# DM3370_OV9782_1-2.net
KiCad netlist of a schematic drawn in Altium Designer
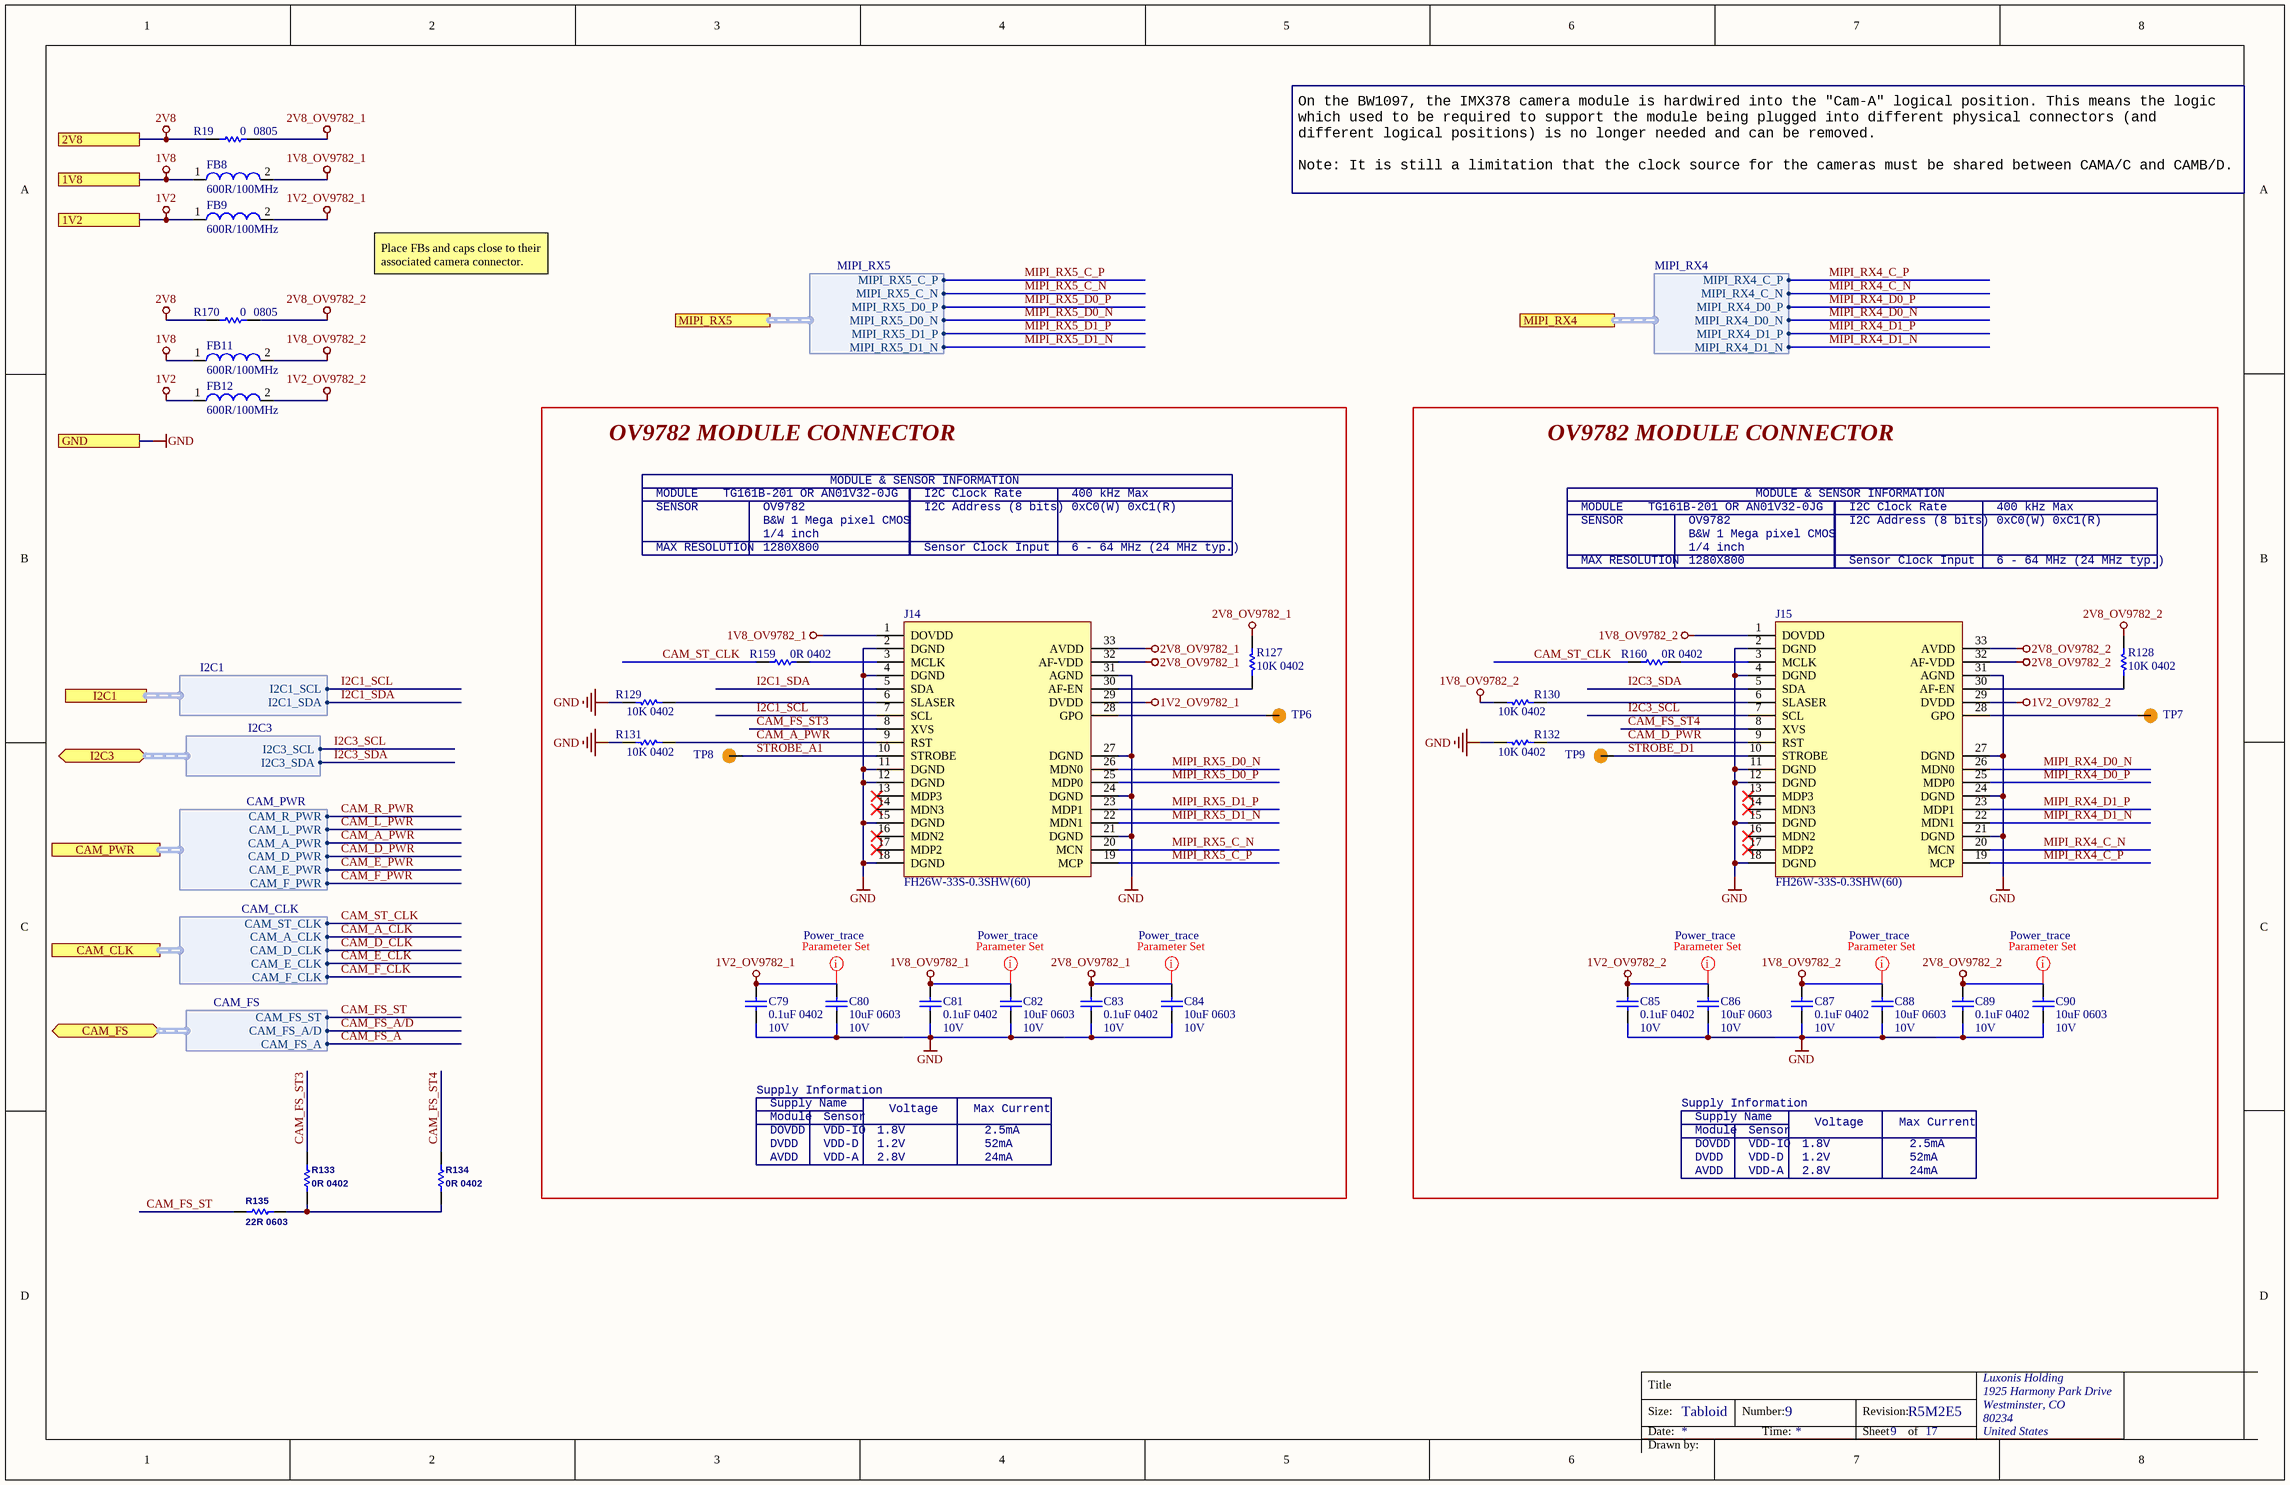
[diagram p0: DM3370_OV9782_1-2.SchDoc]

(export (version "E")
  (design (tool "Eeschema 10.0.6"))
  (components
    (comp (ref "C79")
      (value "0.1uF 0402")
      (footprint "CAP_Altium_Vault_Generic:CAPC0402(1005)70_L")
      (description "CAP CER 0.1UF 10V X7R 0402 5%")
      (fields (field (name "TOLERANCE") "5%") (field (name "VOLTAGE RATING") "10V"))
      (libsource (lib "LuxonisMaster") (part "GRM155R71A104JA01D"))
    )
    (comp (ref "C80")
      (value "10uF 0603")
      (footprint "CAP_Altium_Vault_Generic:CAPC0603(1608)100_L")
      (description "CAP CER 10UF 10V X5R 0603 20%")
      (fields (field (name "TOLERANCE") "20%") (field (name "VOLTAGE RATING") "10V"))
      (libsource (lib "LuxonisMaster") (part "GRM188R61A106ME69D"))
    )
    (comp (ref "C81")
      (value "0.1uF 0402")
      (footprint "CAP_Altium_Vault_Generic:CAPC0402(1005)70_L")
      (description "CAP CER 0.1UF 10V X7R 0402 5%")
      (fields (field (name "TOLERANCE") "5%") (field (name "VOLTAGE RATING") "10V"))
      (libsource (lib "LuxonisMaster") (part "GRM155R71A104JA01D"))
    )
    (comp (ref "C82")
      (value "10uF 0603")
      (footprint "CAP_Altium_Vault_Generic:CAPC0603(1608)100_L")
      (description "CAP CER 10UF 10V X5R 0603 20%")
      (fields (field (name "TOLERANCE") "20%") (field (name "VOLTAGE RATING") "10V"))
      (libsource (lib "LuxonisMaster") (part "GRM188R61A106ME69D"))
    )
    (comp (ref "C83")
      (value "0.1uF 0402")
      (footprint "CAP_Altium_Vault_Generic:CAPC0402(1005)70_L")
      (description "CAP CER 0.1UF 10V X7R 0402 5%")
      (fields (field (name "TOLERANCE") "5%") (field (name "VOLTAGE RATING") "10V"))
      (libsource (lib "LuxonisMaster") (part "GRM155R71A104JA01D"))
    )
    (comp (ref "C84")
      (value "10uF 0603")
      (footprint "CAP_Altium_Vault_Generic:CAPC0603(1608)100_L")
      (description "CAP CER 10UF 10V X5R 0603 20%")
      (fields (field (name "TOLERANCE") "20%") (field (name "VOLTAGE RATING") "10V"))
      (libsource (lib "LuxonisMaster") (part "GRM188R61A106ME69D"))
    )
    (comp (ref "C85")
      (value "0.1uF 0402")
      (footprint "CAP_Altium_Vault_Generic:CAPC0402(1005)70_L")
      (description "CAP CER 0.1UF 10V X7R 0402 5%")
      (fields (field (name "TOLERANCE") "5%") (field (name "VOLTAGE RATING") "10V"))
      (libsource (lib "LuxonisMaster") (part "GRM155R71A104JA01D"))
    )
    (comp (ref "C86")
      (value "10uF 0603")
      (footprint "CAP_Altium_Vault_Generic:CAPC0603(1608)100_L")
      (description "CAP CER 10UF 10V X5R 0603 20%")
      (fields (field (name "TOLERANCE") "20%") (field (name "VOLTAGE RATING") "10V"))
      (libsource (lib "LuxonisMaster") (part "GRM188R61A106ME69D"))
    )
    (comp (ref "C87")
      (value "0.1uF 0402")
      (footprint "CAP_Altium_Vault_Generic:CAPC0402(1005)70_L")
      (description "CAP CER 0.1UF 10V X7R 0402 5%")
      (fields (field (name "TOLERANCE") "5%") (field (name "VOLTAGE RATING") "10V"))
      (libsource (lib "LuxonisMaster") (part "GRM155R71A104JA01D"))
    )
    (comp (ref "C88")
      (value "10uF 0603")
      (footprint "CAP_Altium_Vault_Generic:CAPC0603(1608)100_L")
      (description "CAP CER 10UF 10V X5R 0603 20%")
      (fields (field (name "TOLERANCE") "20%") (field (name "VOLTAGE RATING") "10V"))
      (libsource (lib "LuxonisMaster") (part "GRM188R61A106ME69D"))
    )
    (comp (ref "C89")
      (value "0.1uF 0402")
      (footprint "CAP_Altium_Vault_Generic:CAPC0402(1005)70_L")
      (description "CAP CER 0.1UF 10V X7R 0402 5%")
      (fields (field (name "TOLERANCE") "5%") (field (name "VOLTAGE RATING") "10V"))
      (libsource (lib "LuxonisMaster") (part "GRM155R71A104JA01D"))
    )
    (comp (ref "C90")
      (value "10uF 0603")
      (footprint "CAP_Altium_Vault_Generic:CAPC0603(1608)100_L")
      (description "CAP CER 10UF 10V X5R 0603 20%")
      (fields (field (name "TOLERANCE") "20%") (field (name "VOLTAGE RATING") "10V"))
      (libsource (lib "LuxonisMaster") (part "GRM188R61A106ME69D"))
    )
    (comp (ref "FB8")
      (value "600R/100MHz")
      (footprint "LuxonisMaster:2508056017Y2")
      (description "FERRITE BEAD, 0.1OHM, 2A, 0805, 600R/100MHz")
      (fields (field (name "TOLERANCE") "25%"))
      (libsource (lib "LuxonisMaster") (part "2508056017Y2"))
    )
    (comp (ref "FB9")
      (value "600R/100MHz")
      (footprint "LuxonisMaster:2508056017Y2")
      (description "FERRITE BEAD, 0.1OHM, 2A, 0805, 600R/100MHz")
      (fields (field (name "TOLERANCE") "25%"))
      (libsource (lib "LuxonisMaster") (part "2508056017Y2"))
    )
    (comp (ref "FB11")
      (value "600R/100MHz")
      (footprint "LuxonisMaster:2508056017Y2")
      (description "FERRITE BEAD, 0.1OHM, 2A, 0805, 600R/100MHz")
      (fields (field (name "TOLERANCE") "25%"))
      (libsource (lib "LuxonisMaster") (part "2508056017Y2"))
    )
    (comp (ref "FB12")
      (value "600R/100MHz")
      (footprint "LuxonisMaster:2508056017Y2")
      (description "FERRITE BEAD, 0.1OHM, 2A, 0805, 600R/100MHz")
      (fields (field (name "TOLERANCE") "25%"))
      (libsource (lib "LuxonisMaster") (part "2508056017Y2"))
    )
    (comp (ref "J14")
      (value "FH26W-33S-0.3SHW(60)")
      (footprint "FH26W-33S-0.3SHW(60)")
      (description "FFC/FPC Connector, 33 Contact(s), 1 Row(s), Female, Right Angle, Surface Mount Terminal")
      (libsource (lib "Luxonis LLC") (part "FH26W-33S-0.3SHW(60)"))
    )
    (comp (ref "J15")
      (value "FH26W-33S-0.3SHW(60)")
      (footprint "FH26W-33S-0.3SHW(60)")
      (description "FFC/FPC Connector, 33 Contact(s), 1 Row(s), Female, Right Angle, Surface Mount Terminal")
      (libsource (lib "Luxonis LLC") (part "FH26W-33S-0.3SHW(60)"))
    )
    (comp (ref "R19")
      (value "0")
      (footprint "RESC0805(2012)_L")
      (description "RES SMD 0 OHM 1% 1/8W 0805")
      (fields (field (name "CASE/PACKAGE") "0805") (field (name "Comment") "CRCW08050000Z0EA"))
      (libsource (lib "Luxonis LLC") (part "Default resistor symbol"))
    )
    (comp (ref "R127")
      (value "10K 0402")
      (footprint "RES_Altium_Vault_Generic:RESC0402(1005)_L")
      (fields (field (name "TOLERANCE") "1%"))
      (libsource (lib "LuxonisMaster") (part "RC0402FR-1310KL"))
    )
    (comp (ref "R128")
      (value "10K 0402")
      (footprint "RES_Altium_Vault_Generic:RESC0402(1005)_L")
      (fields (field (name "TOLERANCE") "1%"))
      (libsource (lib "LuxonisMaster") (part "RC0402FR-1310KL"))
    )
    (comp (ref "R129")
      (value "10K 0402")
      (footprint "RES_Altium_Vault_Generic:RESC0402(1005)_L")
      (fields (field (name "TOLERANCE") "1%"))
      (libsource (lib "LuxonisMaster") (part "RC0402FR-1310KL"))
    )
    (comp (ref "R130")
      (value "10K 0402")
      (footprint "RES_Altium_Vault_Generic:RESC0402(1005)_L")
      (fields (field (name "TOLERANCE") "1%"))
      (libsource (lib "LuxonisMaster") (part "RC0402FR-1310KL"))
    )
    (comp (ref "R131")
      (value "10K 0402")
      (footprint "RES_Altium_Vault_Generic:RESC0402(1005)_L")
      (fields (field (name "TOLERANCE") "1%"))
      (libsource (lib "LuxonisMaster") (part "RC0402FR-1310KL"))
    )
    (comp (ref "R132")
      (value "10K 0402")
      (footprint "RES_Altium_Vault_Generic:RESC0402(1005)_L")
      (fields (field (name "TOLERANCE") "1%"))
      (libsource (lib "LuxonisMaster") (part "RC0402FR-1310KL"))
    )
    (comp (ref "R133")
      (value "0R 0402")
      (footprint "RES_Altium_Vault_Generic:RESC0402(1005)_L")
      (description "RES SMD 0 OHM JUMPER 1/16W 0402")
      (fields (field (name "TOLERANCE") "5%"))
      (libsource (lib "LuxonisMaster") (part "CRCW04020000Z0ED"))
    )
    (comp (ref "R134")
      (value "0R 0402")
      (footprint "RES_Altium_Vault_Generic:RESC0402(1005)_L")
      (description "RES SMD 0 OHM JUMPER 1/16W 0402")
      (fields (field (name "TOLERANCE") "5%"))
      (libsource (lib "LuxonisMaster") (part "CRCW04020000Z0ED"))
    )
    (comp (ref "R135")
      (value "22R 0603")
      (footprint "RESC0603(1608)_L")
      (description "RES SMD 22 OHM 1% 1/10W 0603")
      (fields (field (name "TOLERANCE") "1%"))
      (libsource (lib "LuxonisMaster") (part "RC0603FR-0722RL"))
    )
    (comp (ref "R159")
      (value "0R 0402")
      (footprint "RES_Altium_Vault_Generic:RESC0402(1005)_L")
      (description "RES SMD 0 OHM JUMPER 1/16W 0402")
      (fields (field (name "TOLERANCE") "5%"))
      (libsource (lib "LuxonisMaster") (part "CRCW04020000Z0ED"))
    )
    (comp (ref "R160")
      (value "0R 0402")
      (footprint "RES_Altium_Vault_Generic:RESC0402(1005)_L")
      (description "RES SMD 0 OHM JUMPER 1/16W 0402")
      (fields (field (name "TOLERANCE") "5%"))
      (libsource (lib "LuxonisMaster") (part "CRCW04020000Z0ED"))
    )
    (comp (ref "R170")
      (value "0")
      (footprint "RESC0805(2012)_L")
      (description "RES SMD 0 OHM 1% 1/8W 0805")
      (fields (field (name "CASE/PACKAGE") "0805") (field (name "Comment") "CRCW08050000Z0EA"))
      (libsource (lib "Luxonis LLC") (part "Default resistor symbol"))
    )
    (comp (ref "TP6")
      (value "TP100_200_NS")
      (footprint "LuxonisMaster:TP100_200_NS")
      (libsource (lib "LuxonisMaster") (part "TEST_POINT"))
    )
    (comp (ref "TP7")
      (value "TP100_200_NS")
      (footprint "LuxonisMaster:TP100_200_NS")
      (libsource (lib "LuxonisMaster") (part "TEST_POINT"))
    )
    (comp (ref "TP8")
      (value "TP100_200_NS")
      (footprint "LuxonisMaster:TP100_200_NS")
      (libsource (lib "LuxonisMaster") (part "TEST_POINT"))
    )
    (comp (ref "TP9")
      (value "TP100_200_NS")
      (footprint "LuxonisMaster:TP100_200_NS")
      (libsource (lib "LuxonisMaster") (part "TEST_POINT"))
    )
  )
  (nets
    (net (code "9") (name "/CAM_A_PWR") (class "Default")
      (node (ref "J14") (pin "9") (pinfunction "RST_9") (pintype "passive"))
      (node (ref "R131") (pin "1") (pinfunction "1_1") (pintype "passive"))
    )
    (net (code "11") (name "/CAM_D_PWR") (class "Default")
      (node (ref "J15") (pin "9") (pinfunction "RST_9") (pintype "passive"))
      (node (ref "R132") (pin "1") (pinfunction "1_1") (pintype "passive"))
    )
    (net (code "16") (name "/CAM_FS_ST") (class "Default")
      (node (ref "R135") (pin "2") (pinfunction "2_2") (pintype "passive"))
    )
    (net (code "17") (name "/CAM_FS_ST3") (class "Default")
      (node (ref "J14") (pin "8") (pinfunction "XVS_8") (pintype "passive"))
      (node (ref "R133") (pin "2") (pinfunction "2_2") (pintype "passive"))
    )
    (net (code "18") (name "/CAM_FS_ST4") (class "Default")
      (node (ref "J15") (pin "8") (pinfunction "XVS_8") (pintype "passive"))
      (node (ref "R134") (pin "2") (pinfunction "2_2") (pintype "passive"))
    )
    (net (code "23") (name "/CAM_ST_CLK") (class "Default")
      (node (ref "R159") (pin "1") (pinfunction "1_1") (pintype "passive"))
      (node (ref "R160") (pin "1") (pinfunction "1_1") (pintype "passive"))
    )
    (net (code "24") (name "/I2C1_SCL") (class "Default")
      (node (ref "J14") (pin "7") (pinfunction "SCL_7") (pintype "passive"))
    )
    (net (code "25") (name "/I2C1_SDA") (class "Default")
      (node (ref "J14") (pin "5") (pinfunction "SDA_5") (pintype "passive"))
    )
    (net (code "26") (name "/I2C3_SCL") (class "Default")
      (node (ref "J15") (pin "7") (pinfunction "SCL_7") (pintype "passive"))
    )
    (net (code "27") (name "/I2C3_SDA") (class "Default")
      (node (ref "J15") (pin "5") (pinfunction "SDA_5") (pintype "passive"))
    )
    (net (code "28") (name "/MIPI_RX4_C_N") (class "Default")
      (node (ref "J15") (pin "20") (pinfunction "MCN_20") (pintype "passive"))
    )
    (net (code "29") (name "/MIPI_RX4_C_P") (class "Default")
      (node (ref "J15") (pin "19") (pinfunction "MCP_19") (pintype "passive"))
    )
    (net (code "30") (name "/MIPI_RX4_D0_N") (class "Default")
      (node (ref "J15") (pin "26") (pinfunction "MDN0_26") (pintype "passive"))
    )
    (net (code "31") (name "/MIPI_RX4_D0_P") (class "Default")
      (node (ref "J15") (pin "25") (pinfunction "MDP0_25") (pintype "passive"))
    )
    (net (code "32") (name "/MIPI_RX4_D1_N") (class "Default")
      (node (ref "J15") (pin "22") (pinfunction "MDN1_22") (pintype "passive"))
    )
    (net (code "33") (name "/MIPI_RX4_D1_P") (class "Default")
      (node (ref "J15") (pin "23") (pinfunction "MDP1_23") (pintype "passive"))
    )
    (net (code "34") (name "/MIPI_RX5_C_N") (class "Default")
      (node (ref "J14") (pin "20") (pinfunction "MCN_20") (pintype "passive"))
    )
    (net (code "35") (name "/MIPI_RX5_C_P") (class "Default")
      (node (ref "J14") (pin "19") (pinfunction "MCP_19") (pintype "passive"))
    )
    (net (code "36") (name "/MIPI_RX5_D0_N") (class "Default")
      (node (ref "J14") (pin "26") (pinfunction "MDN0_26") (pintype "passive"))
    )
    (net (code "37") (name "/MIPI_RX5_D0_P") (class "Default")
      (node (ref "J14") (pin "25") (pinfunction "MDP0_25") (pintype "passive"))
    )
    (net (code "38") (name "/MIPI_RX5_D1_N") (class "Default")
      (node (ref "J14") (pin "22") (pinfunction "MDN1_22") (pintype "passive"))
    )
    (net (code "39") (name "/MIPI_RX5_D1_P") (class "Default")
      (node (ref "J14") (pin "23") (pinfunction "MDP1_23") (pintype "passive"))
    )
    (net (code "40") (name "/STROBE_A1") (class "Default")
      (node (ref "J14") (pin "10") (pinfunction "STROBE_10") (pintype "passive"))
      (node (ref "TP8") (pin "1") (pintype "passive"))
    )
    (net (code "41") (name "/STROBE_D1") (class "Default")
      (node (ref "J15") (pin "10") (pinfunction "STROBE_10") (pintype "passive"))
      (node (ref "TP9") (pin "1") (pintype "passive"))
    )
    (net (code "49") (name "1V2") (class "Default")
      (node (ref "FB12") (pin "1") (pinfunction "1_1") (pintype "passive"))
      (node (ref "FB9") (pin "1") (pinfunction "1_1") (pintype "passive"))
    )
    (net (code "50") (name "1V2_OV9782_1") (class "Default")
      (node (ref "C79") (pin "2") (pinfunction "2_2") (pintype "passive"))
      (node (ref "C80") (pin "2") (pinfunction "2_2") (pintype "passive"))
      (node (ref "FB9") (pin "2") (pinfunction "2_2") (pintype "passive"))
      (node (ref "J14") (pin "29") (pinfunction "DVDD_29") (pintype "passive"))
    )
    (net (code "51") (name "1V2_OV9782_2") (class "Default")
      (node (ref "C85") (pin "2") (pinfunction "2_2") (pintype "passive"))
      (node (ref "C86") (pin "2") (pinfunction "2_2") (pintype "passive"))
      (node (ref "FB12") (pin "2") (pinfunction "2_2") (pintype "passive"))
      (node (ref "J15") (pin "29") (pinfunction "DVDD_29") (pintype "passive"))
    )
    (net (code "52") (name "1V8") (class "Default")
      (node (ref "FB11") (pin "1") (pinfunction "1_1") (pintype "passive"))
      (node (ref "FB8") (pin "1") (pinfunction "1_1") (pintype "passive"))
    )
    (net (code "53") (name "1V8_OV9782_1") (class "Default")
      (node (ref "C81") (pin "2") (pinfunction "2_2") (pintype "passive"))
      (node (ref "C82") (pin "2") (pinfunction "2_2") (pintype "passive"))
      (node (ref "FB8") (pin "2") (pinfunction "2_2") (pintype "passive"))
      (node (ref "J14") (pin "1") (pinfunction "DOVDD_1") (pintype "passive"))
    )
    (net (code "54") (name "1V8_OV9782_2") (class "Default")
      (node (ref "C87") (pin "2") (pinfunction "2_2") (pintype "passive"))
      (node (ref "C88") (pin "2") (pinfunction "2_2") (pintype "passive"))
      (node (ref "FB11") (pin "2") (pinfunction "2_2") (pintype "passive"))
      (node (ref "J15") (pin "1") (pinfunction "DOVDD_1") (pintype "passive"))
      (node (ref "R130") (pin "2") (pinfunction "2_2") (pintype "passive"))
    )
    (net (code "55") (name "2V8") (class "Default")
      (node (ref "R170") (pin "1") (pinfunction "1_1") (pintype "passive"))
      (node (ref "R19") (pin "1") (pinfunction "1_1") (pintype "passive"))
    )
    (net (code "56") (name "2V8_OV9782_1") (class "Default")
      (node (ref "C83") (pin "2") (pinfunction "2_2") (pintype "passive"))
      (node (ref "C84") (pin "2") (pinfunction "2_2") (pintype "passive"))
      (node (ref "J14") (pin "32") (pinfunction "AF-VDD_32") (pintype "passive"))
      (node (ref "J14") (pin "33") (pinfunction "AVDD_33") (pintype "passive"))
      (node (ref "R127") (pin "1") (pinfunction "1_1") (pintype "passive"))
      (node (ref "R19") (pin "2") (pinfunction "2_2") (pintype "passive"))
    )
    (net (code "57") (name "2V8_OV9782_2") (class "Default")
      (node (ref "C89") (pin "2") (pinfunction "2_2") (pintype "passive"))
      (node (ref "C90") (pin "2") (pinfunction "2_2") (pintype "passive"))
      (node (ref "J15") (pin "32") (pinfunction "AF-VDD_32") (pintype "passive"))
      (node (ref "J15") (pin "33") (pinfunction "AVDD_33") (pintype "passive"))
      (node (ref "R128") (pin "1") (pinfunction "1_1") (pintype "passive"))
      (node (ref "R170") (pin "2") (pinfunction "2_2") (pintype "passive"))
    )
    (net (code "58") (name "GND") (class "Default")
      (node (ref "C79") (pin "1") (pinfunction "1_1") (pintype "passive"))
      (node (ref "C80") (pin "1") (pinfunction "1_1") (pintype "passive"))
      (node (ref "C81") (pin "1") (pinfunction "1_1") (pintype "passive"))
      (node (ref "C82") (pin "1") (pinfunction "1_1") (pintype "passive"))
      (node (ref "C83") (pin "1") (pinfunction "1_1") (pintype "passive"))
      (node (ref "C84") (pin "1") (pinfunction "1_1") (pintype "passive"))
      (node (ref "C85") (pin "1") (pinfunction "1_1") (pintype "passive"))
      (node (ref "C86") (pin "1") (pinfunction "1_1") (pintype "passive"))
      (node (ref "C87") (pin "1") (pinfunction "1_1") (pintype "passive"))
      (node (ref "C88") (pin "1") (pinfunction "1_1") (pintype "passive"))
      (node (ref "C89") (pin "1") (pinfunction "1_1") (pintype "passive"))
      (node (ref "C90") (pin "1") (pinfunction "1_1") (pintype "passive"))
      (node (ref "J14") (pin "11") (pinfunction "DGND_11") (pintype "passive"))
      (node (ref "J14") (pin "12") (pinfunction "DGND_12") (pintype "passive"))
      (node (ref "J14") (pin "15") (pinfunction "DGND_15") (pintype "passive"))
      (node (ref "J14") (pin "18") (pinfunction "DGND_18") (pintype "passive"))
      (node (ref "J14") (pin "2") (pinfunction "DGND_2") (pintype "passive"))
      (node (ref "J14") (pin "21") (pinfunction "DGND_21") (pintype "passive"))
      (node (ref "J14") (pin "24") (pinfunction "DGND_24") (pintype "passive"))
      (node (ref "J14") (pin "27") (pinfunction "DGND_27") (pintype "passive"))
      (node (ref "J14") (pin "31") (pinfunction "AGND_31") (pintype "passive"))
      (node (ref "J14") (pin "4") (pinfunction "DGND_4") (pintype "passive"))
      (node (ref "J15") (pin "11") (pinfunction "DGND_11") (pintype "passive"))
      (node (ref "J15") (pin "12") (pinfunction "DGND_12") (pintype "passive"))
      (node (ref "J15") (pin "15") (pinfunction "DGND_15") (pintype "passive"))
      (node (ref "J15") (pin "18") (pinfunction "DGND_18") (pintype "passive"))
      (node (ref "J15") (pin "2") (pinfunction "DGND_2") (pintype "passive"))
      (node (ref "J15") (pin "21") (pinfunction "DGND_21") (pintype "passive"))
      (node (ref "J15") (pin "24") (pinfunction "DGND_24") (pintype "passive"))
      (node (ref "J15") (pin "27") (pinfunction "DGND_27") (pintype "passive"))
      (node (ref "J15") (pin "31") (pinfunction "AGND_31") (pintype "passive"))
      (node (ref "J15") (pin "4") (pinfunction "DGND_4") (pintype "passive"))
      (node (ref "R129") (pin "2") (pinfunction "2_2") (pintype "passive"))
      (node (ref "R131") (pin "2") (pinfunction "2_2") (pintype "passive"))
      (node (ref "R132") (pin "2") (pinfunction "2_2") (pintype "passive"))
    )
    (net (code "59") (name "Net-(J14-AF-EN)") (class "Default")
      (node (ref "J14") (pin "30") (pinfunction "AF-EN_30") (pintype "passive"))
      (node (ref "R127") (pin "2") (pinfunction "2_2") (pintype "passive"))
    )
    (net (code "60") (name "Net-(J14-GPO)") (class "Default")
      (node (ref "J14") (pin "28") (pinfunction "GPO_28") (pintype "passive"))
      (node (ref "TP6") (pin "1") (pintype "passive"))
    )
    (net (code "61") (name "Net-(J14-MCLK)") (class "Default")
      (node (ref "J14") (pin "3") (pinfunction "MCLK_3") (pintype "passive"))
      (node (ref "R159") (pin "2") (pinfunction "2_2") (pintype "passive"))
    )
    (net (code "62") (name "Net-(J14-SLASER)") (class "Default")
      (node (ref "J14") (pin "6") (pinfunction "SLASER_6") (pintype "passive"))
      (node (ref "R129") (pin "1") (pinfunction "1_1") (pintype "passive"))
    )
    (net (code "63") (name "Net-(J15-AF-EN)") (class "Default")
      (node (ref "J15") (pin "30") (pinfunction "AF-EN_30") (pintype "passive"))
      (node (ref "R128") (pin "2") (pinfunction "2_2") (pintype "passive"))
    )
    (net (code "64") (name "Net-(J15-GPO)") (class "Default")
      (node (ref "J15") (pin "28") (pinfunction "GPO_28") (pintype "passive"))
      (node (ref "TP7") (pin "1") (pintype "passive"))
    )
    (net (code "65") (name "Net-(J15-MCLK)") (class "Default")
      (node (ref "J15") (pin "3") (pinfunction "MCLK_3") (pintype "passive"))
      (node (ref "R160") (pin "2") (pinfunction "2_2") (pintype "passive"))
    )
    (net (code "66") (name "Net-(J15-SLASER)") (class "Default")
      (node (ref "J15") (pin "6") (pinfunction "SLASER_6") (pintype "passive"))
      (node (ref "R130") (pin "1") (pinfunction "1_1") (pintype "passive"))
    )
    (net (code "67") (name "Net-(R133-Pad1)") (class "Default")
      (node (ref "R133") (pin "1") (pinfunction "1_1") (pintype "passive"))
      (node (ref "R134") (pin "1") (pinfunction "1_1") (pintype "passive"))
      (node (ref "R135") (pin "1") (pinfunction "1_1") (pintype "passive"))
    )
    (net (code "68") (name "unconnected-(J14-MDN2-Pad16)") (class "Default")
      (node (ref "J14") (pin "16") (pinfunction "MDN2_16") (pintype "passive+no_connect"))
    )
    (net (code "69") (name "unconnected-(J14-MDN3-Pad14)") (class "Default")
      (node (ref "J14") (pin "14") (pinfunction "MDN3_14") (pintype "passive+no_connect"))
    )
    (net (code "70") (name "unconnected-(J14-MDP2-Pad17)") (class "Default")
      (node (ref "J14") (pin "17") (pinfunction "MDP2_17") (pintype "passive+no_connect"))
    )
    (net (code "71") (name "unconnected-(J14-MDP3-Pad13)") (class "Default")
      (node (ref "J14") (pin "13") (pinfunction "MDP3_13") (pintype "passive+no_connect"))
    )
    (net (code "72") (name "unconnected-(J15-MDN2-Pad16)") (class "Default")
      (node (ref "J15") (pin "16") (pinfunction "MDN2_16") (pintype "passive+no_connect"))
    )
    (net (code "73") (name "unconnected-(J15-MDN3-Pad14)") (class "Default")
      (node (ref "J15") (pin "14") (pinfunction "MDN3_14") (pintype "passive+no_connect"))
    )
    (net (code "74") (name "unconnected-(J15-MDP2-Pad17)") (class "Default")
      (node (ref "J15") (pin "17") (pinfunction "MDP2_17") (pintype "passive+no_connect"))
    )
    (net (code "75") (name "unconnected-(J15-MDP3-Pad13)") (class "Default")
      (node (ref "J15") (pin "13") (pinfunction "MDP3_13") (pintype "passive+no_connect"))
    )
  )
)
